# Adafruit_MCP2221.net
KiCad netlist of a schematic drawn in EAGLE
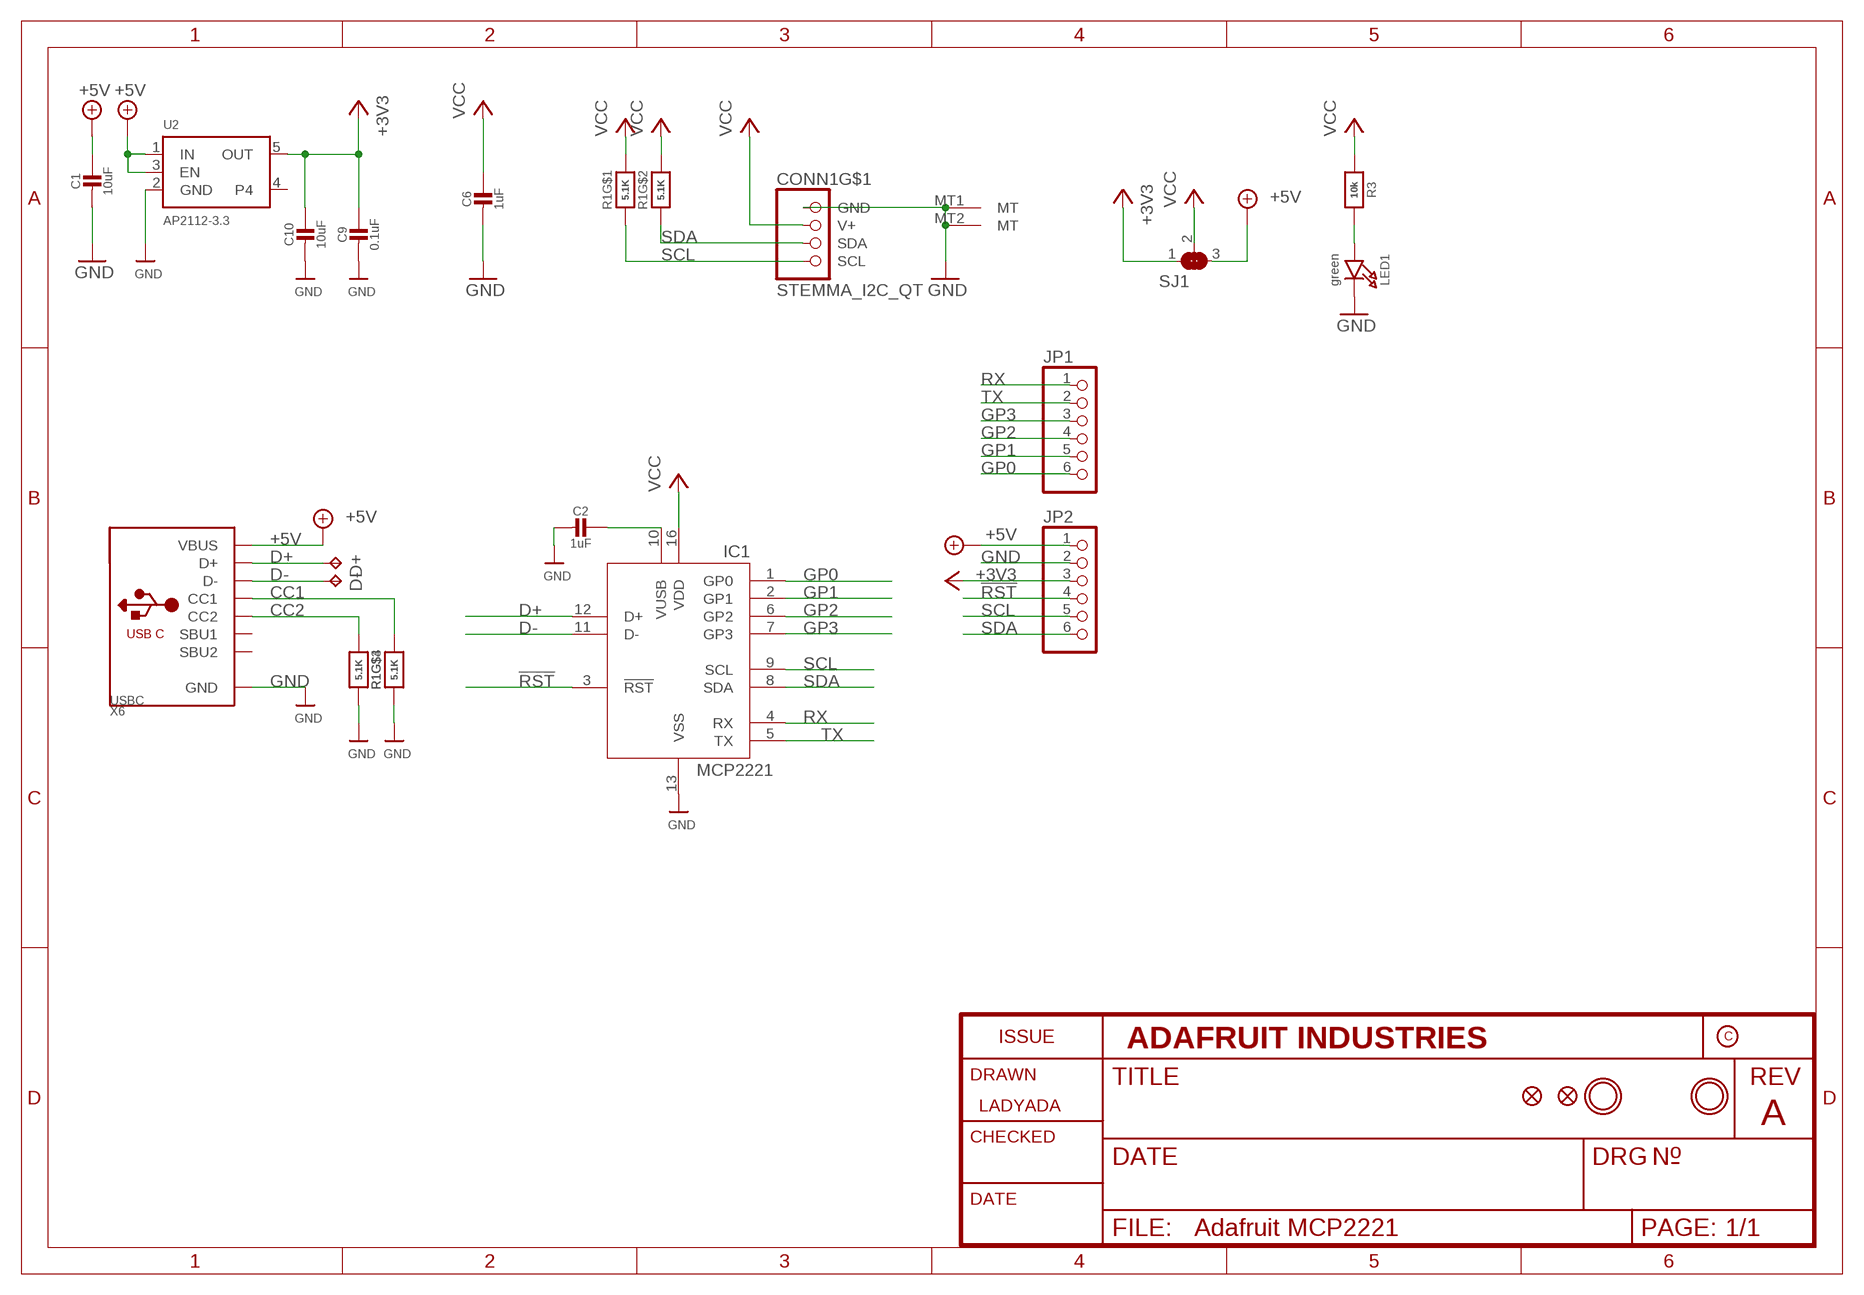
[diagram p0: schematic, sheet 1]

(export (version "E")
  (design (tool "Eeschema 10.0.6"))
  (components
    (comp (ref "C1")
      (value "10uF")
      (footprint "eagle-import:0805-NO")
      (libsource (lib "eagle-import") (part "CAP_CERAMIC0805-NOOUTLINE"))
    )
    (comp (ref "C2")
      (value "1uF")
      (footprint "eagle-import:0603-NO")
      (libsource (lib "eagle-import") (part "CAP_CERAMIC0603_NO"))
    )
    (comp (ref "C6")
      (value "1uF")
      (footprint "eagle-import:0603-NO")
      (libsource (lib "eagle-import") (part "CAP_CERAMIC0603_NO"))
    )
    (comp (ref "C9")
      (value "0.1uF")
      (footprint "eagle-import:0603-NO")
      (libsource (lib "eagle-import") (part "CAP_CERAMIC0603_NO"))
    )
    (comp (ref "C10")
      (value "10uF")
      (footprint "eagle-import:0805-NO")
      (fields (field (name "REV") "A"))
      (libsource (lib "eagle-import") (part "CAP_CERAMIC0805-NOOUTLINE"))
    )
    (comp (ref "CONN1")
      (value "STEMMA_I2C_QT")
      (footprint "eagle-import:JST_SH4")
      (libsource (lib "eagle-import") (part "STEMMA_I2C_QT"))
    )
    (comp (ref "D+")
      (value "TPTP17R")
      (footprint "eagle-import:TP17R")
      (libsource (lib "eagle-import") (part "TPTP17R"))
    )
    (comp (ref "D-")
      (value "TPTP17R")
      (footprint "eagle-import:TP17R")
      (libsource (lib "eagle-import") (part "TPTP17R"))
    )
    (comp (ref "FID1")
      (value "FIDUCIAL_1MM")
      (footprint "eagle-import:FIDUCIAL_1MM")
      (libsource (lib "eagle-import") (part "FIDUCIAL_1MM"))
    )
    (comp (ref "FID2")
      (value "FIDUCIAL_1MM")
      (footprint "eagle-import:FIDUCIAL_1MM")
      (libsource (lib "eagle-import") (part "FIDUCIAL_1MM"))
    )
    (comp (ref "IC1")
      (value "MCP2221_ML")
      (footprint "eagle-import:QFN16_4MM")
      (libsource (lib "eagle-import") (part "MCP2221_ML"))
    )
    (comp (ref "JP1")
      (value "HEADER-1X670MIL")
      (footprint "eagle-import:1X06_ROUND_70")
      (libsource (lib "eagle-import") (part "HEADER-1X670MIL"))
    )
    (comp (ref "JP2")
      (value "HEADER-1X670MIL")
      (footprint "eagle-import:1X06_ROUND_70")
      (libsource (lib "eagle-import") (part "HEADER-1X670MIL"))
    )
    (comp (ref "LED1")
      (value "green")
      (footprint "eagle-import:CHIPLED_0603_NOOUTLINE")
      (libsource (lib "eagle-import") (part "LED0603_NOOUTLINE"))
    )
    (comp (ref "R1")
      (value "5.1K")
      (footprint "eagle-import:RESPACK_4X0603")
      (libsource (lib "eagle-import") (part "RESISTOR_4PACK"))
    )
    (comp (ref "R3")
      (value "10k")
      (footprint "eagle-import:0603-NO")
      (libsource (lib "eagle-import") (part "RESISTOR_0603_NOOUT"))
    )
    (comp (ref "SJ1")
      (value "SOLDERJUMPER_2WAY")
      (footprint "eagle-import:SOLDERJUMPER_2WAY_OPEN_NOPASTE")
      (libsource (lib "eagle-import") (part "SOLDERJUMPER_2WAY"))
    )
    (comp (ref "U$6")
      (value "MOUNTINGHOLE2.5")
      (footprint "eagle-import:MOUNTINGHOLE_2.5_PLATED")
      (fields (field (name "BOM") "EXCLUDE") (field (name "REV") "D"))
      (libsource (lib "eagle-import") (part "MOUNTINGHOLE2.5"))
    )
    (comp (ref "U$7")
      (value "MOUNTINGHOLE2.5")
      (footprint "eagle-import:MOUNTINGHOLE_2.5_PLATED")
      (libsource (lib "eagle-import") (part "MOUNTINGHOLE2.5"))
    )
    (comp (ref "U2")
      (value "AP2112-3.3")
      (footprint "eagle-import:SOT23-5")
      (libsource (lib "eagle-import") (part "VREG_SOT23-5"))
    )
    (comp (ref "X6")
      (value "USBC")
      (footprint "eagle-import:USB_C_CUSB31-CFM2AX-01-X")
      (libsource (lib "eagle-import") (part "USB_C"))
    )
  )
  (nets
    (net (code "1") (name "+3V3") (class "Default")
      (node (ref "C10") (pin "1") (pinfunction "1_1") (pintype "passive"))
      (node (ref "C9") (pin "1") (pinfunction "1_1") (pintype "passive"))
      (node (ref "JP2") (pin "3") (pinfunction "3_3") (pintype "passive"))
      (node (ref "SJ1") (pin "1") (pinfunction "1_1") (pintype "passive"))
      (node (ref "U2") (pin "5") (pinfunction "OUT_5") (pintype "power_in"))
    )
    (net (code "2") (name "+5V") (class "Default")
      (node (ref "C1") (pin "1") (pinfunction "1_1") (pintype "passive"))
      (node (ref "JP2") (pin "1") (pinfunction "1_1") (pintype "passive"))
      (node (ref "SJ1") (pin "3") (pinfunction "3_3") (pintype "passive"))
      (node (ref "U2") (pin "1") (pinfunction "IN_1") (pintype "power_in"))
      (node (ref "U2") (pin "3") (pinfunction "EN_3") (pintype "input"))
      (node (ref "X6") (pin "A4B9") (pinfunction "VBUS_A4B9") (pintype "power_in"))
      (node (ref "X6") (pin "B4A9") (pinfunction "VBUS_B4A9") (pintype "power_in"))
    )
    (net (code "3") (name "/CC1") (class "Default")
      (node (ref "R1") (pin "6") (pinfunction "2_6") (pintype "passive"))
      (node (ref "X6") (pin "A5") (pinfunction "CC1_A5") (pintype "bidirectional"))
    )
    (net (code "4") (name "/CC2") (class "Default")
      (node (ref "R1") (pin "4") (pinfunction "1_4") (pintype "passive"))
      (node (ref "X6") (pin "B5") (pinfunction "CC2_B5") (pintype "bidirectional"))
    )
    (net (code "5") (name "/D+") (class "Default")
      (node (ref "D+") (pin "TP") (pinfunction "TP_TP") (pintype "input"))
      (node (ref "IC1") (pin "12") (pinfunction "D+_12") (pintype "bidirectional"))
      (node (ref "X6") (pin "A6") (pinfunction "D+_A6") (pintype "bidirectional"))
      (node (ref "X6") (pin "B6") (pinfunction "D+_B6") (pintype "bidirectional"))
    )
    (net (code "6") (name "/D-") (class "Default")
      (node (ref "D-") (pin "TP") (pinfunction "TP_TP") (pintype "input"))
      (node (ref "IC1") (pin "11") (pinfunction "D-_11") (pintype "bidirectional"))
      (node (ref "X6") (pin "A7") (pinfunction "D-_A7") (pintype "bidirectional"))
      (node (ref "X6") (pin "B7") (pinfunction "D-_B7") (pintype "bidirectional"))
    )
    (net (code "7") (name "/GP0") (class "Default")
      (node (ref "IC1") (pin "1") (pinfunction "GP0_1") (pintype "bidirectional"))
      (node (ref "JP1") (pin "6") (pinfunction "6_6") (pintype "passive"))
    )
    (net (code "8") (name "/GP1") (class "Default")
      (node (ref "IC1") (pin "2") (pinfunction "GP1_2") (pintype "bidirectional"))
      (node (ref "JP1") (pin "5") (pinfunction "5_5") (pintype "passive"))
    )
    (net (code "9") (name "/GP2") (class "Default")
      (node (ref "IC1") (pin "6") (pinfunction "GP2_6") (pintype "bidirectional"))
      (node (ref "JP1") (pin "4") (pinfunction "4_4") (pintype "passive"))
    )
    (net (code "10") (name "/GP3") (class "Default")
      (node (ref "IC1") (pin "7") (pinfunction "GP3_7") (pintype "bidirectional"))
      (node (ref "JP1") (pin "3") (pinfunction "3_3") (pintype "passive"))
    )
    (net (code "11") (name "/RX") (class "Default")
      (node (ref "IC1") (pin "4") (pinfunction "RX_4") (pintype "bidirectional"))
      (node (ref "JP1") (pin "1") (pinfunction "1_1") (pintype "passive"))
    )
    (net (code "12") (name "/SCL") (class "Default")
      (node (ref "CONN1") (pin "4") (pinfunction "SCL_4") (pintype "passive"))
      (node (ref "IC1") (pin "9") (pinfunction "SCL_9") (pintype "bidirectional"))
      (node (ref "JP2") (pin "5") (pinfunction "5_5") (pintype "passive"))
      (node (ref "R1") (pin "1") (pinfunction "1_1") (pintype "passive"))
    )
    (net (code "13") (name "/SDA") (class "Default")
      (node (ref "CONN1") (pin "3") (pinfunction "SDA_3") (pintype "passive"))
      (node (ref "IC1") (pin "8") (pinfunction "SDA_8") (pintype "bidirectional"))
      (node (ref "JP2") (pin "6") (pinfunction "6_6") (pintype "passive"))
      (node (ref "R1") (pin "2") (pinfunction "1_2") (pintype "passive"))
    )
    (net (code "14") (name "/TX") (class "Default")
      (node (ref "IC1") (pin "5") (pinfunction "TX_5") (pintype "bidirectional"))
      (node (ref "JP1") (pin "2") (pinfunction "2_2") (pintype "passive"))
    )
    (net (code "15") (name "/~{RST}") (class "Default")
      (node (ref "IC1") (pin "3") (pinfunction "~{RST}_3") (pintype "input"))
      (node (ref "JP2") (pin "4") (pinfunction "4_4") (pintype "passive"))
    )
    (net (code "16") (name "GND") (class "Default")
      (node (ref "C1") (pin "2") (pinfunction "2_2") (pintype "passive"))
      (node (ref "C10") (pin "2") (pinfunction "2_2") (pintype "passive"))
      (node (ref "C2") (pin "2") (pinfunction "2_2") (pintype "passive"))
      (node (ref "C6") (pin "2") (pinfunction "2_2") (pintype "passive"))
      (node (ref "C9") (pin "2") (pinfunction "2_2") (pintype "passive"))
      (node (ref "CONN1") (pin "1") (pinfunction "GND_1") (pintype "passive"))
      (node (ref "CONN1") (pin "MT1") (pinfunction "MT_MT1") (pintype "bidirectional"))
      (node (ref "CONN1") (pin "MT2") (pinfunction "MT_MT2") (pintype "bidirectional"))
      (node (ref "IC1") (pin "13") (pinfunction "VSS_13") (pintype "power_in"))
      (node (ref "JP2") (pin "2") (pinfunction "2_2") (pintype "passive"))
      (node (ref "LED1") (pin "C") (pinfunction "C_C") (pintype "passive"))
      (node (ref "R1") (pin "3") (pinfunction "1_3") (pintype "passive"))
      (node (ref "R1") (pin "5") (pinfunction "2_5") (pintype "passive"))
      (node (ref "U2") (pin "2") (pinfunction "GND_2") (pintype "power_in"))
      (node (ref "X6") (pin "A1B12") (pinfunction "GND_A1B12") (pintype "power_in"))
      (node (ref "X6") (pin "B1A12") (pinfunction "GND_B1A12") (pintype "power_in"))
    )
    (net (code "17") (name "Net-(IC1-VUSB)") (class "Default")
      (node (ref "C2") (pin "1") (pinfunction "1_1") (pintype "passive"))
      (node (ref "IC1") (pin "10") (pinfunction "VUSB_10") (pintype "power_in"))
    )
    (net (code "18") (name "Net-(LED1-PadA)") (class "Default")
      (node (ref "LED1") (pin "A") (pinfunction "A_A") (pintype "passive"))
      (node (ref "R3") (pin "2") (pinfunction "2_2") (pintype "passive"))
    )
    (net (code "19") (name "VCC") (class "Default")
      (node (ref "C6") (pin "1") (pinfunction "1_1") (pintype "passive"))
      (node (ref "CONN1") (pin "2") (pinfunction "V+_2") (pintype "passive"))
      (node (ref "IC1") (pin "16") (pinfunction "VDD_16") (pintype "power_in"))
      (node (ref "R1") (pin "7") (pinfunction "2_7") (pintype "passive"))
      (node (ref "R1") (pin "8") (pinfunction "2_8") (pintype "passive"))
      (node (ref "R3") (pin "1") (pinfunction "1_1") (pintype "passive"))
      (node (ref "SJ1") (pin "2") (pinfunction "2_2") (pintype "passive"))
    )
    (net (code "20") (name "unconnected-(U2-P4-Pad4)") (class "Default")
      (node (ref "U2") (pin "4") (pinfunction "P4_4") (pintype "bidirectional"))
    )
    (net (code "21") (name "unconnected-(X6-SBU1-PadA8)") (class "Default")
      (node (ref "X6") (pin "A8") (pinfunction "SBU1_A8") (pintype "bidirectional"))
    )
    (net (code "22") (name "unconnected-(X6-SBU2-PadB8)") (class "Default")
      (node (ref "X6") (pin "B8") (pinfunction "SBU2_B8") (pintype "bidirectional"))
    )
  )
)
